# 4069-Twin-T-Drums-PinConn.net
KiCad netlist of a schematic drawn in EAGLE
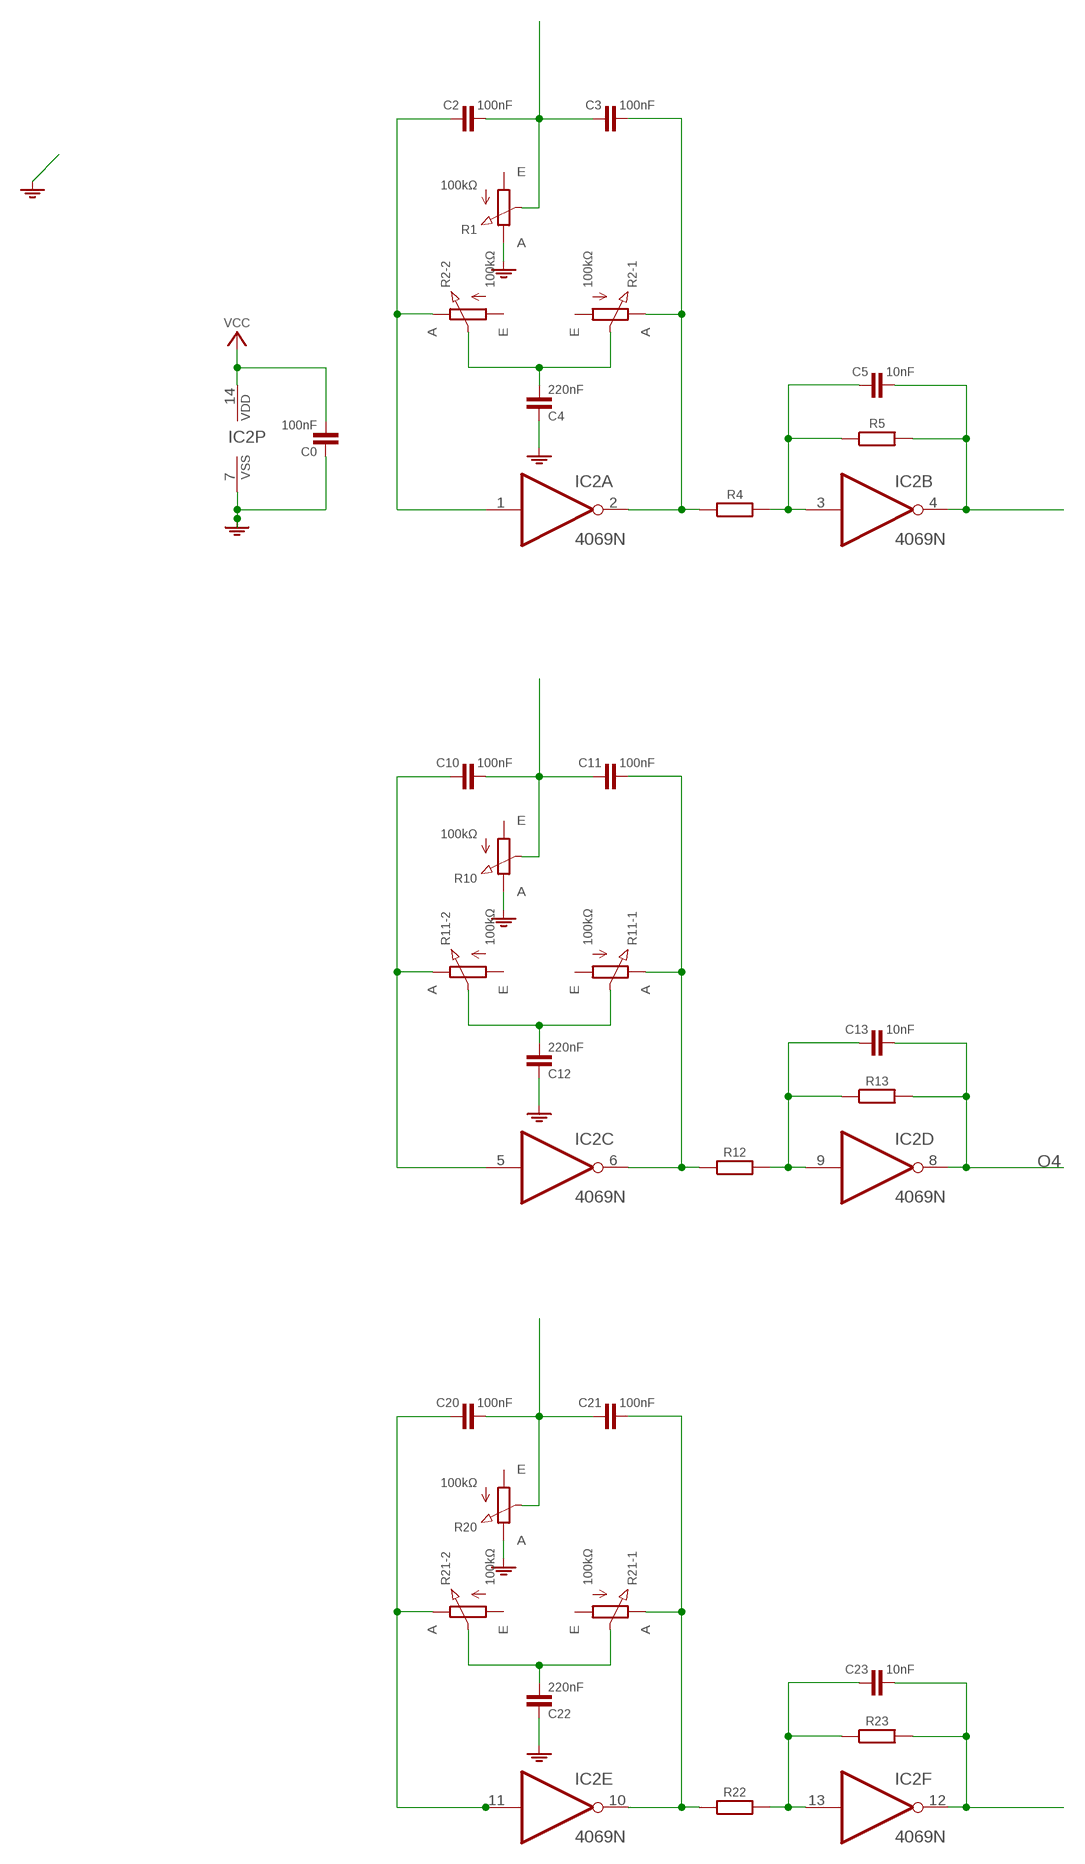
[diagram p0: schematic, sheet 1]

(export (version "E")
  (design (tool "Eeschema 10.0.6"))
  (components
    (comp (ref "C0")
      (value "100nF")
      (footprint "eagle-import:C050-020X044_V")
      (libsource (lib "eagle-import") (part "C050-020X044/V"))
    )
    (comp (ref "C2")
      (value "100nF")
      (footprint "eagle-import:C050-020X044")
      (libsource (lib "eagle-import") (part "C-H050-020X044"))
    )
    (comp (ref "C3")
      (value "100nF")
      (footprint "eagle-import:C050-020X044")
      (libsource (lib "eagle-import") (part "C-H050-020X044"))
    )
    (comp (ref "C4")
      (value "220nF")
      (footprint "eagle-import:C050-020X044_V")
      (libsource (lib "eagle-import") (part "C050-020X044/V"))
    )
    (comp (ref "C5")
      (value "10nF")
      (footprint "eagle-import:C025-015X024")
      (libsource (lib "eagle-import") (part "C-H025-015X024"))
    )
    (comp (ref "C10")
      (value "100nF")
      (footprint "eagle-import:C050-020X044")
      (libsource (lib "eagle-import") (part "C-H050-020X044"))
    )
    (comp (ref "C11")
      (value "100nF")
      (footprint "eagle-import:C050-020X044")
      (libsource (lib "eagle-import") (part "C-H050-020X044"))
    )
    (comp (ref "C12")
      (value "220nF")
      (footprint "eagle-import:C050-020X044_V")
      (libsource (lib "eagle-import") (part "C050-020X044/V"))
    )
    (comp (ref "C13")
      (value "10nF")
      (footprint "eagle-import:C025-015X024")
      (libsource (lib "eagle-import") (part "C-H025-015X024"))
    )
    (comp (ref "C20")
      (value "100nF")
      (footprint "eagle-import:C050-020X044")
      (libsource (lib "eagle-import") (part "C-H050-020X044"))
    )
    (comp (ref "C21")
      (value "100nF")
      (footprint "eagle-import:C050-020X044")
      (libsource (lib "eagle-import") (part "C-H050-020X044"))
    )
    (comp (ref "C22")
      (value "220nF")
      (footprint "eagle-import:C050-020X044_V")
      (libsource (lib "eagle-import") (part "C050-020X044/V"))
    )
    (comp (ref "C23")
      (value "10nF")
      (footprint "eagle-import:C025-015X024")
      (libsource (lib "eagle-import") (part "C-H025-015X024"))
    )
    (comp (ref "IC2")
      (value "4069N")
      (footprint "eagle-import:DIL14")
      (libsource (lib "eagle-import") (part "4069N"))
    )
    (comp (ref "R1")
      (value "100kΩ")
      (footprint "eagle-import:CONN-3P")
      (libsource (lib "eagle-import") (part "POT-3P"))
    )
    (comp (ref "R2")
      (value "100kΩ")
      (footprint "eagle-import:CONN-2X3P")
      (libsource (lib "eagle-import") (part "POT-STEREO2X3P"))
    )
    (comp (ref "R4")
      (value "R-H0202/2V")
      (footprint "eagle-import:0202_2V")
      (libsource (lib "eagle-import") (part "R-H0202/2V"))
    )
    (comp (ref "R5")
      (value "R-H0202/2V")
      (footprint "eagle-import:0202_2V")
      (libsource (lib "eagle-import") (part "R-H0202/2V"))
    )
    (comp (ref "R10")
      (value "100kΩ")
      (footprint "eagle-import:CONN-3P")
      (libsource (lib "eagle-import") (part "POT-3P"))
    )
    (comp (ref "R11")
      (value "100kΩ")
      (footprint "eagle-import:CONN-2X3P")
      (libsource (lib "eagle-import") (part "POT-STEREO2X3P"))
    )
    (comp (ref "R12")
      (value "R-H0202/2")
      (footprint "eagle-import:0202_2")
      (libsource (lib "eagle-import") (part "R-H0202/2"))
    )
    (comp (ref "R13")
      (value "R-H0202/2V")
      (footprint "eagle-import:0202_2V")
      (libsource (lib "eagle-import") (part "R-H0202/2V"))
    )
    (comp (ref "R20")
      (value "100kΩ")
      (footprint "eagle-import:CONN-3P")
      (libsource (lib "eagle-import") (part "POT-3P"))
    )
    (comp (ref "R21")
      (value "100kΩ")
      (footprint "eagle-import:CONN-2X3P")
      (libsource (lib "eagle-import") (part "POT-STEREO2X3P"))
    )
    (comp (ref "R22")
      (value "R-H0202/2V")
      (footprint "eagle-import:0202_2V")
      (libsource (lib "eagle-import") (part "R-H0202/2V"))
    )
    (comp (ref "R23")
      (value "R-H0202/2V")
      (footprint "eagle-import:0202_2V")
      (libsource (lib "eagle-import") (part "R-H0202/2V"))
    )
    (comp (ref "S12")
      (value "VCC_GNDPWR-L")
      (footprint "eagle-import:PWR-L")
      (libsource (lib "eagle-import") (part "VCC_GNDPWR-L"))
    )
  )
  (nets
    (net (code "1") (name "/O4") (class "Default")
      (node (ref "C13") (pin "2") (pinfunction "2_2") (pintype "passive"))
      (node (ref "IC2") (pin "8") (pinfunction "O_8") (pintype "output"))
      (node (ref "R13") (pin "2") (pinfunction "2_2") (pintype "passive"))
    )
    (net (code "2") (name "GND") (class "Default")
      (node (ref "C0") (pin "1") (pinfunction "1_1") (pintype "passive"))
      (node (ref "C12") (pin "1") (pinfunction "1_1") (pintype "passive"))
      (node (ref "C22") (pin "1") (pinfunction "1_1") (pintype "passive"))
      (node (ref "C4") (pin "1") (pinfunction "1_1") (pintype "passive"))
      (node (ref "IC2") (pin "7") (pinfunction "VSS_7") (pintype "power_in"))
      (node (ref "R1") (pin "3") (pinfunction "E_3") (pintype "passive"))
      (node (ref "R10") (pin "3") (pinfunction "E_3") (pintype "passive"))
      (node (ref "R20") (pin "3") (pinfunction "E_3") (pintype "passive"))
      (node (ref "S12") (pin "1") (pinfunction "GND_1") (pintype "power_in"))
    )
    (net (code "3") (name "Net-(IC2A-I)") (class "Default")
      (node (ref "C2") (pin "1") (pinfunction "1_1") (pintype "passive"))
      (node (ref "IC2") (pin "1") (pinfunction "I_1") (pintype "input"))
      (node (ref "R2") (pin "5") (pinfunction "E_5") (pintype "passive"))
    )
    (net (code "4") (name "Net-(IC2A-O)") (class "Default")
      (node (ref "C3") (pin "2") (pinfunction "2_2") (pintype "passive"))
      (node (ref "IC2") (pin "2") (pinfunction "O_2") (pintype "output"))
      (node (ref "R2") (pin "2") (pinfunction "E_2") (pintype "passive"))
      (node (ref "R4") (pin "1") (pinfunction "1_1") (pintype "passive"))
    )
    (net (code "5") (name "Net-(IC2B-I)") (class "Default")
      (node (ref "C5") (pin "1") (pinfunction "1_1") (pintype "passive"))
      (node (ref "IC2") (pin "3") (pinfunction "I_3") (pintype "input"))
      (node (ref "R4") (pin "2") (pinfunction "2_2") (pintype "passive"))
      (node (ref "R5") (pin "1") (pinfunction "1_1") (pintype "passive"))
    )
    (net (code "6") (name "Net-(IC2B-O)") (class "Default")
      (node (ref "C5") (pin "2") (pinfunction "2_2") (pintype "passive"))
      (node (ref "IC2") (pin "4") (pinfunction "O_4") (pintype "output"))
      (node (ref "R5") (pin "2") (pinfunction "2_2") (pintype "passive"))
    )
    (net (code "7") (name "Net-(IC2C-I)") (class "Default")
      (node (ref "C10") (pin "1") (pinfunction "1_1") (pintype "passive"))
      (node (ref "IC2") (pin "5") (pinfunction "I_5") (pintype "input"))
      (node (ref "R11") (pin "5") (pinfunction "E_5") (pintype "passive"))
    )
    (net (code "8") (name "Net-(IC2C-O)") (class "Default")
      (node (ref "C11") (pin "2") (pinfunction "2_2") (pintype "passive"))
      (node (ref "IC2") (pin "6") (pinfunction "O_6") (pintype "output"))
      (node (ref "R11") (pin "2") (pinfunction "E_2") (pintype "passive"))
      (node (ref "R12") (pin "1") (pinfunction "1_1") (pintype "passive"))
    )
    (net (code "9") (name "Net-(IC2D-I)") (class "Default")
      (node (ref "C13") (pin "1") (pinfunction "1_1") (pintype "passive"))
      (node (ref "IC2") (pin "9") (pinfunction "I_9") (pintype "input"))
      (node (ref "R12") (pin "2") (pinfunction "2_2") (pintype "passive"))
      (node (ref "R13") (pin "1") (pinfunction "1_1") (pintype "passive"))
    )
    (net (code "10") (name "Net-(IC2E-I)") (class "Default")
      (node (ref "C20") (pin "1") (pinfunction "1_1") (pintype "passive"))
      (node (ref "IC2") (pin "11") (pinfunction "I_11") (pintype "input"))
      (node (ref "R21") (pin "5") (pinfunction "E_5") (pintype "passive"))
    )
    (net (code "11") (name "Net-(IC2E-O)") (class "Default")
      (node (ref "C21") (pin "2") (pinfunction "2_2") (pintype "passive"))
      (node (ref "IC2") (pin "10") (pinfunction "O_10") (pintype "output"))
      (node (ref "R21") (pin "2") (pinfunction "E_2") (pintype "passive"))
      (node (ref "R22") (pin "1") (pinfunction "1_1") (pintype "passive"))
    )
    (net (code "12") (name "Net-(IC2F-I)") (class "Default")
      (node (ref "C23") (pin "1") (pinfunction "1_1") (pintype "passive"))
      (node (ref "IC2") (pin "13") (pinfunction "I_13") (pintype "input"))
      (node (ref "R22") (pin "2") (pinfunction "2_2") (pintype "passive"))
      (node (ref "R23") (pin "1") (pinfunction "1_1") (pintype "passive"))
    )
    (net (code "13") (name "Net-(IC2F-O)") (class "Default")
      (node (ref "C23") (pin "2") (pinfunction "2_2") (pintype "passive"))
      (node (ref "IC2") (pin "12") (pinfunction "O_12") (pintype "output"))
      (node (ref "R23") (pin "2") (pinfunction "2_2") (pintype "passive"))
    )
    (net (code "14") (name "Net-(IC2G-VDD)") (class "Default")
      (node (ref "C0") (pin "2") (pinfunction "2_2") (pintype "passive"))
      (node (ref "IC2") (pin "14") (pinfunction "VDD_14") (pintype "power_in"))
      (node (ref "S12") (pin "2") (pinfunction "VCC_2") (pintype "power_in"))
    )
    (net (code "15") (name "Net-(R1-S)") (class "Default")
      (node (ref "C2") (pin "2") (pinfunction "2_2") (pintype "passive"))
      (node (ref "C3") (pin "1") (pinfunction "1_1") (pintype "passive"))
      (node (ref "R1") (pin "2") (pinfunction "S_2") (pintype "passive"))
    )
    (net (code "16") (name "Net-(R2A-S)") (class "Default")
      (node (ref "C4") (pin "2") (pinfunction "2_2") (pintype "passive"))
      (node (ref "R2") (pin "3") (pinfunction "S_3") (pintype "passive"))
      (node (ref "R2") (pin "6") (pinfunction "S_6") (pintype "passive"))
    )
    (net (code "17") (name "Net-(R10-S)") (class "Default")
      (node (ref "C10") (pin "2") (pinfunction "2_2") (pintype "passive"))
      (node (ref "C11") (pin "1") (pinfunction "1_1") (pintype "passive"))
      (node (ref "R10") (pin "2") (pinfunction "S_2") (pintype "passive"))
    )
    (net (code "18") (name "Net-(R11A-S)") (class "Default")
      (node (ref "C12") (pin "2") (pinfunction "2_2") (pintype "passive"))
      (node (ref "R11") (pin "3") (pinfunction "S_3") (pintype "passive"))
      (node (ref "R11") (pin "6") (pinfunction "S_6") (pintype "passive"))
    )
    (net (code "19") (name "Net-(R20-S)") (class "Default")
      (node (ref "C20") (pin "2") (pinfunction "2_2") (pintype "passive"))
      (node (ref "C21") (pin "1") (pinfunction "1_1") (pintype "passive"))
      (node (ref "R20") (pin "2") (pinfunction "S_2") (pintype "passive"))
    )
    (net (code "20") (name "Net-(R21A-S)") (class "Default")
      (node (ref "C22") (pin "2") (pinfunction "2_2") (pintype "passive"))
      (node (ref "R21") (pin "3") (pinfunction "S_3") (pintype "passive"))
      (node (ref "R21") (pin "6") (pinfunction "S_6") (pintype "passive"))
    )
    (net (code "21") (name "unconnected-(R1-A-Pad1)") (class "Default")
      (node (ref "R1") (pin "1") (pinfunction "A_1") (pintype "passive"))
    )
    (net (code "22") (name "unconnected-(R2A-A-Pad1)") (class "Default")
      (node (ref "R2") (pin "1") (pinfunction "A_1") (pintype "passive"))
    )
    (net (code "23") (name "unconnected-(R2B-A-Pad4)") (class "Default")
      (node (ref "R2") (pin "4") (pinfunction "A_4") (pintype "passive"))
    )
    (net (code "24") (name "unconnected-(R10-A-Pad1)") (class "Default")
      (node (ref "R10") (pin "1") (pinfunction "A_1") (pintype "passive"))
    )
    (net (code "25") (name "unconnected-(R11A-A-Pad1)") (class "Default")
      (node (ref "R11") (pin "1") (pinfunction "A_1") (pintype "passive"))
    )
    (net (code "26") (name "unconnected-(R11B-A-Pad4)") (class "Default")
      (node (ref "R11") (pin "4") (pinfunction "A_4") (pintype "passive"))
    )
    (net (code "27") (name "unconnected-(R20-A-Pad1)") (class "Default")
      (node (ref "R20") (pin "1") (pinfunction "A_1") (pintype "passive"))
    )
    (net (code "28") (name "unconnected-(R21A-A-Pad1)") (class "Default")
      (node (ref "R21") (pin "1") (pinfunction "A_1") (pintype "passive"))
    )
    (net (code "29") (name "unconnected-(R21B-A-Pad4)") (class "Default")
      (node (ref "R21") (pin "4") (pinfunction "A_4") (pintype "passive"))
    )
  )
)
